# esp_round_lcd.net
KiCad netlist of a schematic drawn in EAGLE
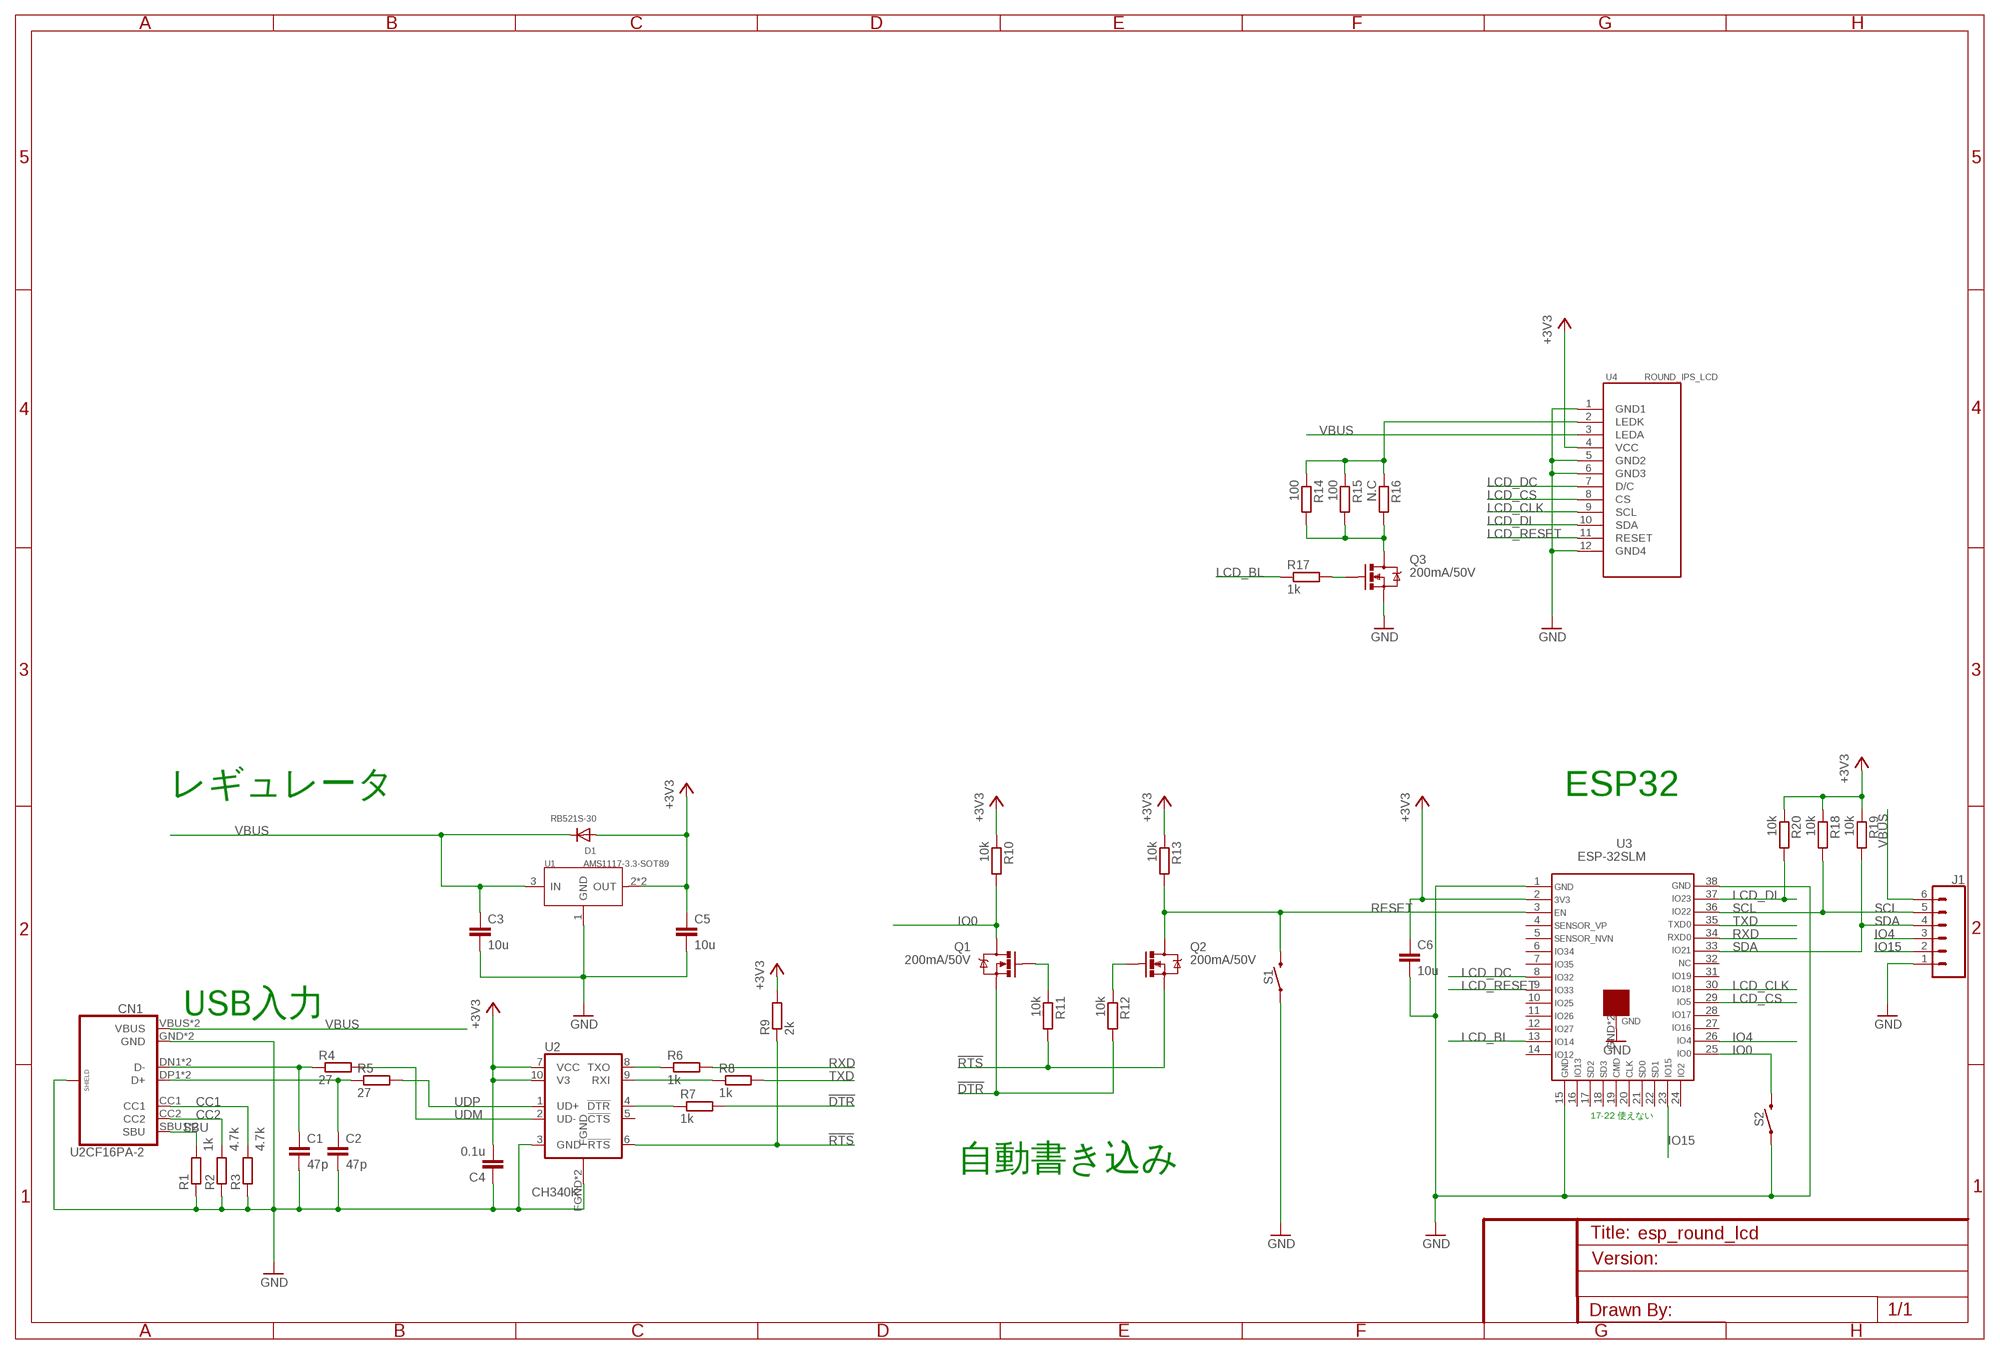
[diagram p0: schematic, sheet 1]

(export (version "E")
  (design (tool "Eeschema 10.0.6"))
  (components
    (comp (ref "C1")
      (value "47p")
      (footprint "eagle-import:C1608")
      (libsource (lib "eagle-import") (part "C-EU-C1608"))
    )
    (comp (ref "C2")
      (value "47p")
      (footprint "eagle-import:C1608")
      (libsource (lib "eagle-import") (part "C-EU-C1608"))
    )
    (comp (ref "C3")
      (value "10u")
      (footprint "eagle-import:C1608")
      (libsource (lib "eagle-import") (part "C-EU-C1608"))
    )
    (comp (ref "C4")
      (value "0.1u")
      (footprint "eagle-import:C1608")
      (libsource (lib "eagle-import") (part "C-EU-C1608"))
    )
    (comp (ref "C5")
      (value "10u")
      (footprint "eagle-import:C1608")
      (libsource (lib "eagle-import") (part "C-EU-C1608"))
    )
    (comp (ref "C6")
      (value "10u")
      (footprint "eagle-import:C1608")
      (libsource (lib "eagle-import") (part "C-EU-C1608"))
    )
    (comp (ref "CN1")
      (value "U2CF16PA-2")
      (footprint "eagle-import:U2CF16PA")
      (libsource (lib "eagle-import") (part "U2CF16PA-2"))
    )
    (comp (ref "D1")
      (value "RB521S-30")
      (footprint "eagle-import:SOD-523")
      (libsource (lib "eagle-import") (part "DIODESOD-523"))
    )
    (comp (ref "J1")
      (value "CONN_06SILK_FEMALE_PTH")
      (footprint "eagle-import:1X06")
      (libsource (lib "eagle-import") (part "CONN_06SILK_FEMALE_PTH"))
    )
    (comp (ref "Q1")
      (value "200mA/50V")
      (footprint "eagle-import:SOT23-3")
      (libsource (lib "eagle-import") (part "MOSFET-NCHANNELBSS138"))
    )
    (comp (ref "Q2")
      (value "200mA/50V")
      (footprint "eagle-import:SOT23-3")
      (libsource (lib "eagle-import") (part "MOSFET-NCHANNELBSS138"))
    )
    (comp (ref "Q3")
      (value "200mA/50V")
      (footprint "eagle-import:SOT23-3")
      (libsource (lib "eagle-import") (part "suna_lib_MOSFET-NCHANNELBSS138"))
    )
    (comp (ref "R1")
      (value "1k")
      (footprint "eagle-import:R0603")
      (libsource (lib "eagle-import") (part "R-EU_R0603"))
    )
    (comp (ref "R2")
      (value "4.7k")
      (footprint "eagle-import:R0603")
      (libsource (lib "eagle-import") (part "R-EU_R0603"))
    )
    (comp (ref "R3")
      (value "4.7k")
      (footprint "eagle-import:R0603")
      (libsource (lib "eagle-import") (part "R-EU_R0603"))
    )
    (comp (ref "R4")
      (value "27")
      (footprint "eagle-import:R0603")
      (libsource (lib "eagle-import") (part "R-EU_R0603"))
    )
    (comp (ref "R5")
      (value "27")
      (footprint "eagle-import:R0603")
      (libsource (lib "eagle-import") (part "R-EU_R0603"))
    )
    (comp (ref "R6")
      (value "1k")
      (footprint "eagle-import:R0603")
      (libsource (lib "eagle-import") (part "R-EU_R0603"))
    )
    (comp (ref "R7")
      (value "1k")
      (footprint "eagle-import:R0603")
      (libsource (lib "eagle-import") (part "R-EU_R0603"))
    )
    (comp (ref "R8")
      (value "1k")
      (footprint "eagle-import:R0603")
      (libsource (lib "eagle-import") (part "R-EU_R0603"))
    )
    (comp (ref "R9")
      (value "2k")
      (footprint "eagle-import:R0603")
      (libsource (lib "eagle-import") (part "R-EU_R0603"))
    )
    (comp (ref "R10")
      (value "10k")
      (footprint "eagle-import:R0603")
      (libsource (lib "eagle-import") (part "R-EU_R0603"))
    )
    (comp (ref "R11")
      (value "10k")
      (footprint "eagle-import:R0603")
      (libsource (lib "eagle-import") (part "R-EU_R0603"))
    )
    (comp (ref "R12")
      (value "10k")
      (footprint "eagle-import:R0603")
      (libsource (lib "eagle-import") (part "R-EU_R0603"))
    )
    (comp (ref "R13")
      (value "10k")
      (footprint "eagle-import:R0603")
      (libsource (lib "eagle-import") (part "R-EU_R0603"))
    )
    (comp (ref "R14")
      (value "100")
      (footprint "eagle-import:R0603")
      (libsource (lib "eagle-import") (part "R-EU_R0603"))
    )
    (comp (ref "R15")
      (value "100")
      (footprint "eagle-import:R0603")
      (libsource (lib "eagle-import") (part "R-EU_R0603"))
    )
    (comp (ref "R16")
      (value "N.C")
      (footprint "eagle-import:R0603")
      (libsource (lib "eagle-import") (part "R-EU_R0603"))
    )
    (comp (ref "R17")
      (value "1k")
      (footprint "eagle-import:R0603")
      (libsource (lib "eagle-import") (part "R-EU_R0603"))
    )
    (comp (ref "R18")
      (value "10k")
      (footprint "eagle-import:R0603")
      (libsource (lib "eagle-import") (part "R-EU_R0603"))
    )
    (comp (ref "R19")
      (value "10k")
      (footprint "eagle-import:R0603")
      (libsource (lib "eagle-import") (part "R-EU_R0603"))
    )
    (comp (ref "R20")
      (value "10k")
      (footprint "eagle-import:R0603")
      (libsource (lib "eagle-import") (part "R-EU_R0603"))
    )
    (comp (ref "S1")
      (value "TACT_SW_3X4")
      (footprint "eagle-import:TACTILE_SWITCH_SMD_3X4MM")
      (libsource (lib "eagle-import") (part "TACT_SW_3X4"))
    )
    (comp (ref "S2")
      (value "TACT_SW_3X4")
      (footprint "eagle-import:TACTILE_SWITCH_SMD_3X4MM")
      (libsource (lib "eagle-import") (part "TACT_SW_3X4"))
    )
    (comp (ref "U1")
      (value "AMS1117-3.3-SOT89")
      (footprint "eagle-import:SOT-89")
      (fields (field (name "MPN") "AMS1117-3.3"))
      (libsource (lib "eagle-import") (part "AMS1117-3.3(SOT-89)"))
    )
    (comp (ref "U2")
      (value "CH340K")
      (footprint "eagle-import:ESSOP10")
      (libsource (lib "eagle-import") (part "CH340K"))
    )
    (comp (ref "U3")
      (value "ESP-32SLM")
      (footprint "eagle-import:ESP32D-SLM")
      (libsource (lib "eagle-import") (part "ESP-32SLM"))
    )
    (comp (ref "U4")
      (value "ROUND_IPS_LCD")
      (footprint "eagle-import:ROUND_IPS_LCD")
      (libsource (lib "eagle-import") (part "ROUND_IPS_LCD"))
    )
  )
  (nets
    (net (code "1") (name "+3V3") (class "Default")
      (node (ref "C4") (pin "2") (pinfunction "2_2") (pintype "passive"))
      (node (ref "C5") (pin "1") (pinfunction "1_1") (pintype "passive"))
      (node (ref "C6") (pin "1") (pinfunction "1_1") (pintype "passive"))
      (node (ref "D1") (pin "A") (pinfunction "A_A") (pintype "passive"))
      (node (ref "R10") (pin "1") (pinfunction "1_1") (pintype "passive"))
      (node (ref "R13") (pin "1") (pinfunction "1_1") (pintype "passive"))
      (node (ref "R18") (pin "1") (pinfunction "1_1") (pintype "passive"))
      (node (ref "R19") (pin "1") (pinfunction "1_1") (pintype "passive"))
      (node (ref "R20") (pin "1") (pinfunction "1_1") (pintype "passive"))
      (node (ref "R9") (pin "2") (pinfunction "2_2") (pintype "passive"))
      (node (ref "U1") (pin "2") (pinfunction "OUT_2") (pintype "bidirectional"))
      (node (ref "U1") (pin "4") (pinfunction "OUT_4") (pintype "bidirectional"))
      (node (ref "U2") (pin "10") (pinfunction "V3_10") (pintype "bidirectional"))
      (node (ref "U2") (pin "7") (pinfunction "VCC_7") (pintype "bidirectional"))
      (node (ref "U3") (pin "2") (pinfunction "2_2") (pintype "bidirectional"))
      (node (ref "U4") (pin "4") (pinfunction "VCC_4") (pintype "power_in"))
    )
    (net (code "2") (name "/CC1") (class "Default")
      (node (ref "CN1") (pin "CC1") (pinfunction "CC1_CC1") (pintype "bidirectional"))
      (node (ref "R3") (pin "2") (pinfunction "2_2") (pintype "passive"))
    )
    (net (code "3") (name "/CC2") (class "Default")
      (node (ref "CN1") (pin "CC2") (pinfunction "CC2_CC2") (pintype "bidirectional"))
      (node (ref "R2") (pin "2") (pinfunction "2_2") (pintype "passive"))
    )
    (net (code "4") (name "/IO0") (class "Default")
      (node (ref "Q1") (pin "3") (pinfunction "D_3") (pintype "passive"))
      (node (ref "R10") (pin "2") (pinfunction "2_2") (pintype "passive"))
      (node (ref "S2") (pin "3") (pinfunction "2_3") (pintype "passive"))
      (node (ref "S2") (pin "4") (pinfunction "2_4") (pintype "passive"))
      (node (ref "U3") (pin "25") (pinfunction "25_25") (pintype "bidirectional"))
    )
    (net (code "5") (name "/IO4") (class "Default")
      (node (ref "J1") (pin "3") (pinfunction "3_3") (pintype "passive"))
      (node (ref "U3") (pin "26") (pinfunction "26_26") (pintype "bidirectional"))
    )
    (net (code "6") (name "/IO15") (class "Default")
      (node (ref "J1") (pin "2") (pinfunction "2_2") (pintype "passive"))
      (node (ref "U3") (pin "23") (pinfunction "23_23") (pintype "bidirectional"))
    )
    (net (code "7") (name "/LCD_BL") (class "Default")
      (node (ref "R17") (pin "1") (pinfunction "1_1") (pintype "passive"))
      (node (ref "U3") (pin "13") (pinfunction "13_13") (pintype "bidirectional"))
    )
    (net (code "8") (name "/LCD_CLK") (class "Default")
      (node (ref "U3") (pin "30") (pinfunction "30_30") (pintype "bidirectional"))
      (node (ref "U4") (pin "9") (pinfunction "SCL_9") (pintype "input"))
    )
    (net (code "9") (name "/LCD_CS") (class "Default")
      (node (ref "U3") (pin "29") (pinfunction "29_29") (pintype "bidirectional"))
      (node (ref "U4") (pin "8") (pinfunction "CS_8") (pintype "input"))
    )
    (net (code "10") (name "/LCD_DC") (class "Default")
      (node (ref "U3") (pin "8") (pinfunction "8_8") (pintype "bidirectional"))
      (node (ref "U4") (pin "7") (pinfunction "D/C_7") (pintype "input"))
    )
    (net (code "11") (name "/LCD_DI") (class "Default")
      (node (ref "R20") (pin "2") (pinfunction "2_2") (pintype "passive"))
      (node (ref "U3") (pin "37") (pinfunction "37_37") (pintype "bidirectional"))
      (node (ref "U4") (pin "10") (pinfunction "SDA_10") (pintype "bidirectional"))
    )
    (net (code "12") (name "/LCD_RESET") (class "Default")
      (node (ref "U3") (pin "9") (pinfunction "9_9") (pintype "bidirectional"))
      (node (ref "U4") (pin "11") (pinfunction "RESET_11") (pintype "input"))
    )
    (net (code "13") (name "/RESET") (class "Default")
      (node (ref "Q2") (pin "3") (pinfunction "D_3") (pintype "passive"))
      (node (ref "R13") (pin "2") (pinfunction "2_2") (pintype "passive"))
      (node (ref "S1") (pin "3") (pinfunction "2_3") (pintype "passive"))
      (node (ref "S1") (pin "4") (pinfunction "2_4") (pintype "passive"))
      (node (ref "U3") (pin "3") (pinfunction "3_3") (pintype "bidirectional"))
    )
    (net (code "14") (name "/RXD") (class "Default")
      (node (ref "R6") (pin "2") (pinfunction "2_2") (pintype "passive"))
      (node (ref "U3") (pin "34") (pinfunction "34_34") (pintype "bidirectional"))
    )
    (net (code "15") (name "/SBU") (class "Default")
      (node (ref "CN1") (pin "SBU1") (pinfunction "SBU_SBU1") (pintype "bidirectional"))
      (node (ref "CN1") (pin "SBU2") (pinfunction "SBU_SBU2") (pintype "bidirectional"))
      (node (ref "R1") (pin "2") (pinfunction "2_2") (pintype "passive"))
    )
    (net (code "16") (name "/SCL") (class "Default")
      (node (ref "J1") (pin "5") (pinfunction "5_5") (pintype "passive"))
      (node (ref "R18") (pin "2") (pinfunction "2_2") (pintype "passive"))
      (node (ref "U3") (pin "36") (pinfunction "36_36") (pintype "bidirectional"))
    )
    (net (code "17") (name "/SDA") (class "Default")
      (node (ref "J1") (pin "4") (pinfunction "4_4") (pintype "passive"))
      (node (ref "R19") (pin "2") (pinfunction "2_2") (pintype "passive"))
      (node (ref "U3") (pin "33") (pinfunction "33_33") (pintype "bidirectional"))
    )
    (net (code "18") (name "/TXD") (class "Default")
      (node (ref "R8") (pin "2") (pinfunction "2_2") (pintype "passive"))
      (node (ref "U3") (pin "35") (pinfunction "35_35") (pintype "bidirectional"))
    )
    (net (code "19") (name "/UDM") (class "Default")
      (node (ref "R4") (pin "2") (pinfunction "2_2") (pintype "passive"))
      (node (ref "U2") (pin "2") (pinfunction "UD-_2") (pintype "bidirectional"))
    )
    (net (code "20") (name "/UDP") (class "Default")
      (node (ref "R5") (pin "2") (pinfunction "2_2") (pintype "passive"))
      (node (ref "U2") (pin "1") (pinfunction "UD+_1") (pintype "bidirectional"))
    )
    (net (code "21") (name "/VBUS") (class "Default")
      (node (ref "C3") (pin "1") (pinfunction "1_1") (pintype "passive"))
      (node (ref "CN1") (pin "VBUS") (pinfunction "VBUS_VBUS") (pintype "power_in"))
      (node (ref "CN1") (pin "VBUS1") (pinfunction "VBUS_VBUS1") (pintype "power_in"))
      (node (ref "D1") (pin "K") (pinfunction "C_K") (pintype "passive"))
      (node (ref "J1") (pin "6") (pinfunction "6_6") (pintype "passive"))
      (node (ref "U1") (pin "3") (pinfunction "IN_3") (pintype "bidirectional"))
      (node (ref "U4") (pin "3") (pinfunction "LEDA_3") (pintype "bidirectional"))
    )
    (net (code "22") (name "/~{DTR}") (class "Default")
      (node (ref "Q1") (pin "2") (pinfunction "S_2") (pintype "passive"))
      (node (ref "R12") (pin "2") (pinfunction "2_2") (pintype "passive"))
      (node (ref "R7") (pin "2") (pinfunction "2_2") (pintype "passive"))
    )
    (net (code "23") (name "/~{RTS}") (class "Default")
      (node (ref "Q2") (pin "2") (pinfunction "S_2") (pintype "passive"))
      (node (ref "R11") (pin "2") (pinfunction "2_2") (pintype "passive"))
      (node (ref "R9") (pin "1") (pinfunction "1_1") (pintype "passive"))
      (node (ref "U2") (pin "6") (pinfunction "~{RTS}_6") (pintype "bidirectional"))
    )
    (net (code "24") (name "GND") (class "Default")
      (node (ref "C1") (pin "2") (pinfunction "2_2") (pintype "passive"))
      (node (ref "C2") (pin "2") (pinfunction "2_2") (pintype "passive"))
      (node (ref "C3") (pin "2") (pinfunction "2_2") (pintype "passive"))
      (node (ref "C4") (pin "1") (pinfunction "1_1") (pintype "passive"))
      (node (ref "C5") (pin "2") (pinfunction "2_2") (pintype "passive"))
      (node (ref "C6") (pin "2") (pinfunction "2_2") (pintype "passive"))
      (node (ref "CN1") (pin "GND") (pinfunction "GND_GND") (pintype "power_in"))
      (node (ref "CN1") (pin "GND1") (pinfunction "GND_GND1") (pintype "power_in"))
      (node (ref "CN1") (pin "GND@10") (pinfunction "SHIELD_GND@10") (pintype "power_in"))
      (node (ref "CN1") (pin "GND@11") (pinfunction "SHIELD_GND@11") (pintype "power_in"))
      (node (ref "CN1") (pin "GND@12") (pinfunction "SHIELD_GND@12") (pintype "power_in"))
      (node (ref "CN1") (pin "GND@13") (pinfunction "SHIELD_GND@13") (pintype "power_in"))
      (node (ref "CN1") (pin "GND@14") (pinfunction "SHIELD_GND@14") (pintype "power_in"))
      (node (ref "CN1") (pin "GND@15") (pinfunction "SHIELD_GND@15") (pintype "power_in"))
      (node (ref "CN1") (pin "GND@16") (pinfunction "SHIELD_GND@16") (pintype "power_in"))
      (node (ref "CN1") (pin "GND@9") (pinfunction "SHIELD_GND@9") (pintype "power_in"))
      (node (ref "J1") (pin "1") (pinfunction "1_1") (pintype "passive"))
      (node (ref "Q3") (pin "2") (pinfunction "S_2") (pintype "passive"))
      (node (ref "R1") (pin "1") (pinfunction "1_1") (pintype "passive"))
      (node (ref "R2") (pin "1") (pinfunction "1_1") (pintype "passive"))
      (node (ref "R3") (pin "1") (pinfunction "1_1") (pintype "passive"))
      (node (ref "S1") (pin "1") (pinfunction "1_1") (pintype "passive"))
      (node (ref "S1") (pin "2") (pinfunction "1_2") (pintype "passive"))
      (node (ref "S2") (pin "1") (pinfunction "1_1") (pintype "passive"))
      (node (ref "S2") (pin "2") (pinfunction "1_2") (pintype "passive"))
      (node (ref "U1") (pin "1") (pinfunction "GND_1") (pintype "bidirectional"))
      (node (ref "U2") (pin "3") (pinfunction "GND_3") (pintype "bidirectional"))
      (node (ref "U2") (pin "FGND") (pinfunction "FGND_FGND") (pintype "bidirectional"))
      (node (ref "U2") (pin "FGND2") (pinfunction "FGND_FGND2") (pintype "bidirectional"))
      (node (ref "U3") (pin "1") (pinfunction "1_1") (pintype "bidirectional"))
      (node (ref "U3") (pin "15") (pinfunction "15_15") (pintype "bidirectional"))
      (node (ref "U3") (pin "38") (pinfunction "38_38") (pintype "bidirectional"))
      (node (ref "U3") (pin "GND") (pinfunction "39_GND") (pintype "bidirectional"))
      (node (ref "U3") (pin "GND2") (pinfunction "39_GND2") (pintype "bidirectional"))
      (node (ref "U4") (pin "1") (pinfunction "GND1_1") (pintype "power_in"))
      (node (ref "U4") (pin "12") (pinfunction "GND4_12") (pintype "power_in"))
      (node (ref "U4") (pin "5") (pinfunction "GND2_5") (pintype "power_in"))
      (node (ref "U4") (pin "6") (pinfunction "GND3_6") (pintype "power_in"))
    )
    (net (code "25") (name "Net-(C1-Pad1)") (class "Default")
      (node (ref "C1") (pin "1") (pinfunction "1_1") (pintype "passive"))
      (node (ref "CN1") (pin "DN1") (pinfunction "D-_DN1") (pintype "bidirectional"))
      (node (ref "CN1") (pin "DN2") (pinfunction "D-_DN2") (pintype "bidirectional"))
      (node (ref "R4") (pin "1") (pinfunction "1_1") (pintype "passive"))
    )
    (net (code "26") (name "Net-(C2-Pad1)") (class "Default")
      (node (ref "C2") (pin "1") (pinfunction "1_1") (pintype "passive"))
      (node (ref "CN1") (pin "DP1") (pinfunction "D+_DP1") (pintype "bidirectional"))
      (node (ref "CN1") (pin "DP2") (pinfunction "D+_DP2") (pintype "bidirectional"))
      (node (ref "R5") (pin "1") (pinfunction "1_1") (pintype "passive"))
    )
    (net (code "27") (name "Net-(Q1-G)") (class "Default")
      (node (ref "Q1") (pin "1") (pinfunction "G_1") (pintype "passive"))
      (node (ref "R11") (pin "1") (pinfunction "1_1") (pintype "passive"))
    )
    (net (code "28") (name "Net-(Q2-G)") (class "Default")
      (node (ref "Q2") (pin "1") (pinfunction "G_1") (pintype "passive"))
      (node (ref "R12") (pin "1") (pinfunction "1_1") (pintype "passive"))
    )
    (net (code "29") (name "Net-(Q3-D)") (class "Default")
      (node (ref "Q3") (pin "3") (pinfunction "D_3") (pintype "passive"))
      (node (ref "R14") (pin "2") (pinfunction "2_2") (pintype "passive"))
      (node (ref "R15") (pin "2") (pinfunction "2_2") (pintype "passive"))
      (node (ref "R16") (pin "2") (pinfunction "2_2") (pintype "passive"))
    )
    (net (code "30") (name "Net-(Q3-G)") (class "Default")
      (node (ref "Q3") (pin "1") (pinfunction "G_1") (pintype "passive"))
      (node (ref "R17") (pin "2") (pinfunction "2_2") (pintype "passive"))
    )
    (net (code "31") (name "Net-(U2-RXI)") (class "Default")
      (node (ref "R8") (pin "1") (pinfunction "1_1") (pintype "passive"))
      (node (ref "U2") (pin "9") (pinfunction "RXI_9") (pintype "bidirectional"))
    )
    (net (code "32") (name "Net-(U2-TXO)") (class "Default")
      (node (ref "R6") (pin "1") (pinfunction "1_1") (pintype "passive"))
      (node (ref "U2") (pin "8") (pinfunction "TXO_8") (pintype "bidirectional"))
    )
    (net (code "33") (name "Net-(U2-~{DTR})") (class "Default")
      (node (ref "R7") (pin "1") (pinfunction "1_1") (pintype "passive"))
      (node (ref "U2") (pin "4") (pinfunction "~{DTR}_4") (pintype "bidirectional"))
    )
    (net (code "34") (name "Net-(U4-LEDK)") (class "Default")
      (node (ref "R14") (pin "1") (pinfunction "1_1") (pintype "passive"))
      (node (ref "R15") (pin "1") (pinfunction "1_1") (pintype "passive"))
      (node (ref "R16") (pin "1") (pinfunction "1_1") (pintype "passive"))
      (node (ref "U4") (pin "2") (pinfunction "LEDK_2") (pintype "bidirectional"))
    )
    (net (code "35") (name "unconnected-(U2-~{CTS}-Pad5)") (class "Default")
      (node (ref "U2") (pin "5") (pinfunction "~{CTS}_5") (pintype "bidirectional"))
    )
    (net (code "36") (name "unconnected-(U3-Pad4)") (class "Default")
      (node (ref "U3") (pin "4") (pinfunction "4_4") (pintype "bidirectional"))
    )
    (net (code "37") (name "unconnected-(U3-Pad5)") (class "Default")
      (node (ref "U3") (pin "5") (pinfunction "5_5") (pintype "bidirectional"))
    )
    (net (code "38") (name "unconnected-(U3-Pad6)") (class "Default")
      (node (ref "U3") (pin "6") (pinfunction "6_6") (pintype "bidirectional"))
    )
    (net (code "39") (name "unconnected-(U3-Pad7)") (class "Default")
      (node (ref "U3") (pin "7") (pinfunction "7_7") (pintype "bidirectional"))
    )
    (net (code "40") (name "unconnected-(U3-Pad10)") (class "Default")
      (node (ref "U3") (pin "10") (pinfunction "10_10") (pintype "bidirectional"))
    )
    (net (code "41") (name "unconnected-(U3-Pad11)") (class "Default")
      (node (ref "U3") (pin "11") (pinfunction "11_11") (pintype "bidirectional"))
    )
    (net (code "42") (name "unconnected-(U3-Pad12)") (class "Default")
      (node (ref "U3") (pin "12") (pinfunction "12_12") (pintype "bidirectional"))
    )
    (net (code "43") (name "unconnected-(U3-Pad14)") (class "Default")
      (node (ref "U3") (pin "14") (pinfunction "14_14") (pintype "bidirectional"))
    )
    (net (code "44") (name "unconnected-(U3-Pad16)") (class "Default")
      (node (ref "U3") (pin "16") (pinfunction "16_16") (pintype "bidirectional"))
    )
    (net (code "45") (name "unconnected-(U3-Pad17)") (class "Default")
      (node (ref "U3") (pin "17") (pinfunction "17_17") (pintype "bidirectional"))
    )
    (net (code "46") (name "unconnected-(U3-Pad18)") (class "Default")
      (node (ref "U3") (pin "18") (pinfunction "18_18") (pintype "bidirectional"))
    )
    (net (code "47") (name "unconnected-(U3-Pad19)") (class "Default")
      (node (ref "U3") (pin "19") (pinfunction "19_19") (pintype "bidirectional"))
    )
    (net (code "48") (name "unconnected-(U3-Pad20)") (class "Default")
      (node (ref "U3") (pin "20") (pinfunction "20_20") (pintype "bidirectional"))
    )
    (net (code "49") (name "unconnected-(U3-Pad21)") (class "Default")
      (node (ref "U3") (pin "21") (pinfunction "21_21") (pintype "bidirectional"))
    )
    (net (code "50") (name "unconnected-(U3-Pad22)") (class "Default")
      (node (ref "U3") (pin "22") (pinfunction "22_22") (pintype "bidirectional"))
    )
    (net (code "51") (name "unconnected-(U3-Pad24)") (class "Default")
      (node (ref "U3") (pin "24") (pinfunction "24_24") (pintype "bidirectional"))
    )
    (net (code "52") (name "unconnected-(U3-Pad27)") (class "Default")
      (node (ref "U3") (pin "27") (pinfunction "27_27") (pintype "bidirectional"))
    )
    (net (code "53") (name "unconnected-(U3-Pad28)") (class "Default")
      (node (ref "U3") (pin "28") (pinfunction "28_28") (pintype "bidirectional"))
    )
    (net (code "54") (name "unconnected-(U3-Pad31)") (class "Default")
      (node (ref "U3") (pin "31") (pinfunction "31_31") (pintype "bidirectional"))
    )
    (net (code "55") (name "unconnected-(U3-Pad32)") (class "Default")
      (node (ref "U3") (pin "32") (pinfunction "32_32") (pintype "bidirectional"))
    )
  )
)
